# Bike_sharing_system_final_one_with_30_pi.net
KiCad netlist of a schematic drawn in EasyEDA
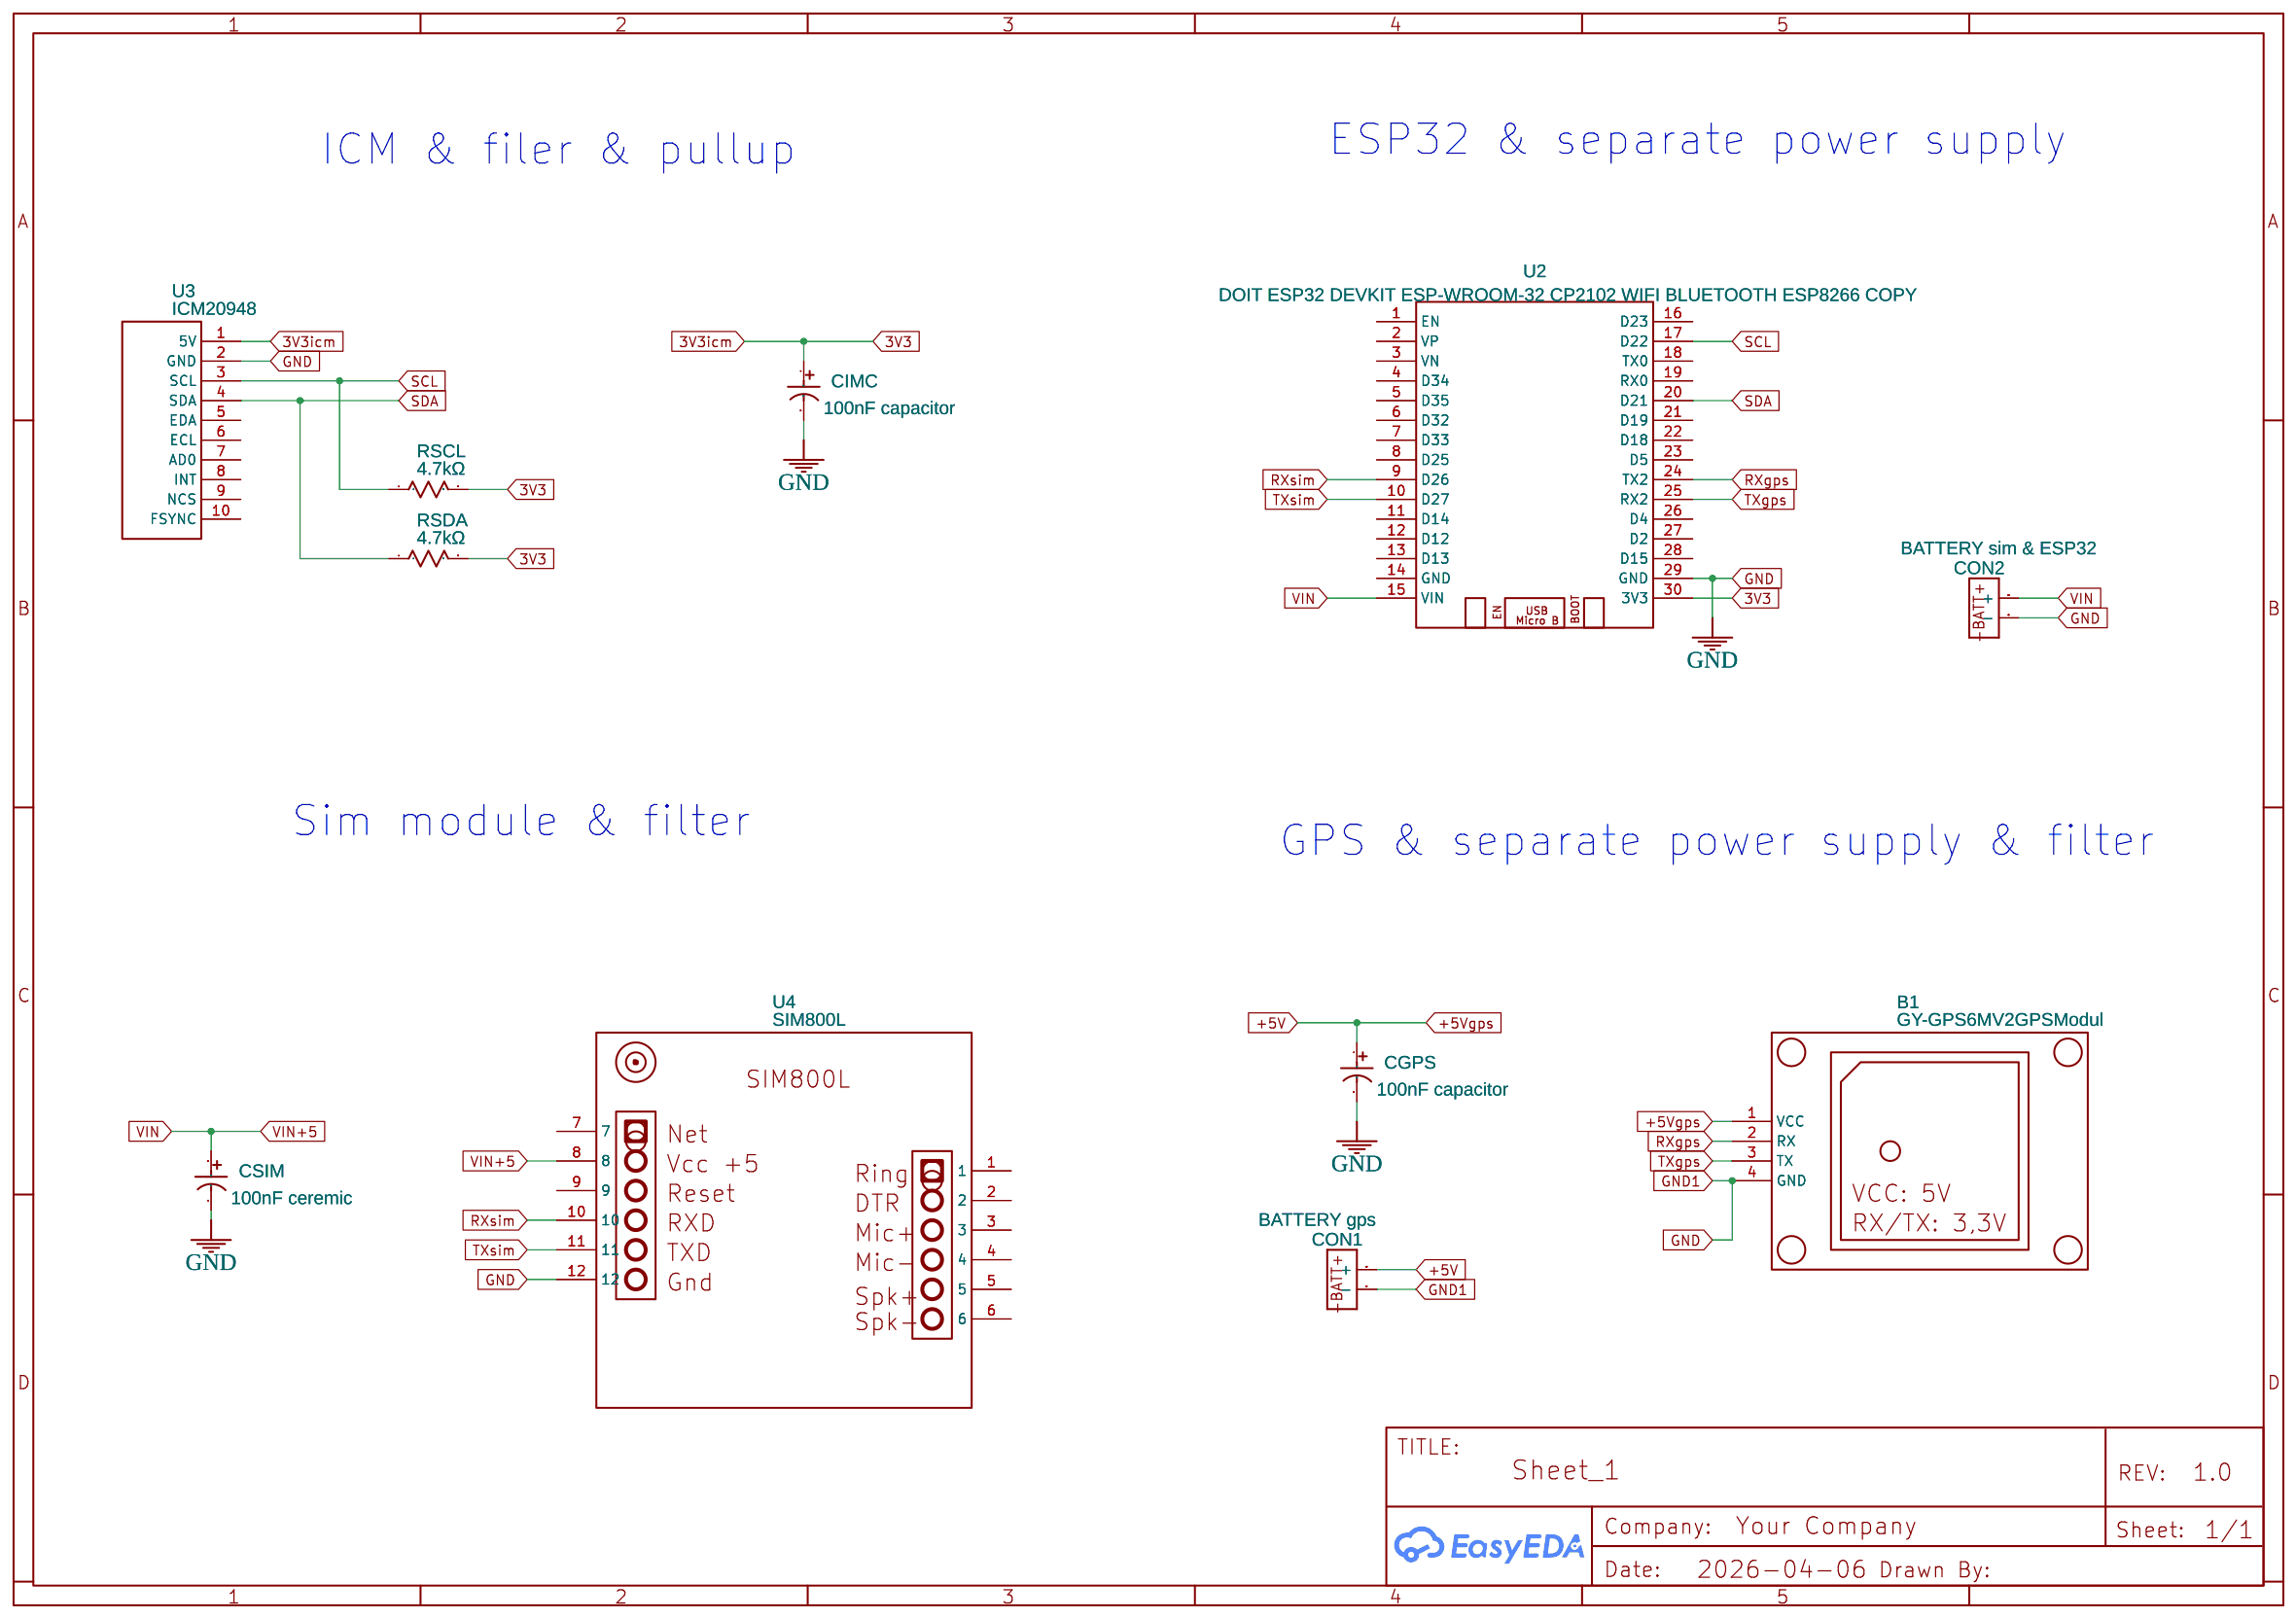
[diagram p0: schematic sheet]

(export (version "E")
  (design (tool "Eeschema 10.0.6"))
  (components
    (comp (ref "B1") (value "GY-GPS6MV2GPSModul") (libsource (lib "") (part "GY-GPS6MV2GPSModul")))
    (comp (ref "CGPS")
      (value "100nF capacitor")
      (fields
        (field (name "Manufacturer Part") "KM476M016D11RR0VH2FP0")
        (field (name "Manufacturer") "CX(承兴)")
      )
      (libsource (lib "") (part "CAPACITOR 680UF COPY"))
    )
    (comp (ref "CIMC")
      (value "100nF capacitor")
      (fields
        (field (name "Manufacturer Part") "KM476M016D11RR0VH2FP0")
        (field (name "Manufacturer") "CX(承兴)")
      )
      (libsource (lib "") (part "CAPACITOR 680UF COPY_2"))
    )
    (comp (ref "CON1") (value "BATTERY gps") (libsource (lib "") (part "2 PIN CON (BATTERY)")))
    (comp (ref "CON2") (value "BATTERY sim & ESP32") (libsource (lib "") (part "2 PIN CON (BATTERY)")))
    (comp (ref "CSIM")
      (value "100nF ceremic")
      (fields
        (field (name "Manufacturer Part") "KM476M016D11RR0VH2FP0")
        (field (name "Manufacturer") "CX(承兴)")
      )
      (libsource (lib "") (part "CAPACITOR 680UF COPY_1"))
    )
    (comp (ref "RSCL")
      (value "4.7kΩ")
      (fields (field (name "Manufacturer Part") "Resister"))
      (libsource (lib "") (part "RESISTER COPY_1"))
    )
    (comp (ref "RSDA")
      (value "4.7kΩ")
      (fields (field (name "Manufacturer Part") "Resister"))
      (libsource (lib "") (part "RESISTER COPY"))
    )
    (comp (ref "U2")
      (value "DOIT ESP32 DEVKIT ESP-WROOM-32 CP2102 WIFI BLUETOOTH ESP8266 COPY")
      (libsource (lib "") (part "DOIT ESP32 DEVKIT ESP-WROOM-32 CP2102 WIFI BLUETOOTH ESP8266 COPY"))
    )
    (comp (ref "U3") (value "ICM20948") (libsource (lib "") (part "ICM20948")))
    (comp (ref "U4") (value "SIM800L") (libsource (lib "") (part "SIM800L")))
  )
  (nets
    (net (code "1") (name "+5V") (class "Default")
      (node (ref "B1") (pin "1") (pinfunction "VCC_1") (pintype "unspecified"))
      (node (ref "CGPS") (pin "1") (pinfunction "1_1") (pintype "unspecified"))
      (node (ref "CON1") (pin "BAT+") (pinfunction "+_BAT+") (pintype "unspecified"))
    )
    (net (code "2") (name "3V3") (class "Default")
      (node (ref "CIMC") (pin "1") (pinfunction "1_1") (pintype "unspecified"))
      (node (ref "RSCL") (pin "2") (pinfunction "2_2") (pintype "unspecified"))
      (node (ref "RSDA") (pin "2") (pinfunction "2_2") (pintype "unspecified"))
      (node (ref "U2") (pin "30") (pinfunction "3V3_30") (pintype "bidirectional"))
      (node (ref "U3") (pin "1") (pinfunction "5V_1") (pintype "unspecified"))
    )
    (net (code "3") (name "GND") (class "Default")
      (node (ref "B1") (pin "4") (pinfunction "GND_4") (pintype "unspecified"))
      (node (ref "CGPS") (pin "2") (pinfunction "2_2") (pintype "unspecified"))
      (node (ref "CIMC") (pin "2") (pinfunction "2_2") (pintype "unspecified"))
      (node (ref "CON1") (pin "BAT-") (pinfunction "-_BAT-") (pintype "unspecified"))
      (node (ref "CON2") (pin "BAT-") (pinfunction "-_BAT-") (pintype "unspecified"))
      (node (ref "CSIM") (pin "2") (pinfunction "2_2") (pintype "unspecified"))
      (node (ref "U2") (pin "29") (pinfunction "GND_29") (pintype "bidirectional"))
      (node (ref "U3") (pin "2") (pinfunction "GND_2") (pintype "unspecified"))
      (node (ref "U4") (pin "12") (pinfunction "12_12") (pintype "unspecified"))
    )
    (net (code "4") (name "RXgps") (class "Default")
      (node (ref "B1") (pin "2") (pinfunction "RX_2") (pintype "unspecified"))
      (node (ref "U2") (pin "24") (pinfunction "TX2_24") (pintype "bidirectional"))
    )
    (net (code "5") (name "RXsim") (class "Default")
      (node (ref "U2") (pin "9") (pinfunction "D26_9") (pintype "bidirectional"))
      (node (ref "U4") (pin "10") (pinfunction "10_10") (pintype "unspecified"))
    )
    (net (code "6") (name "SCL") (class "Default")
      (node (ref "RSCL") (pin "1") (pinfunction "1_1") (pintype "unspecified"))
      (node (ref "U2") (pin "17") (pinfunction "D22_17") (pintype "bidirectional"))
      (node (ref "U3") (pin "3") (pinfunction "SCL_3") (pintype "unspecified"))
    )
    (net (code "7") (name "SDA") (class "Default")
      (node (ref "RSDA") (pin "1") (pinfunction "1_1") (pintype "unspecified"))
      (node (ref "U2") (pin "20") (pinfunction "D21_20") (pintype "bidirectional"))
      (node (ref "U3") (pin "4") (pinfunction "SDA_4") (pintype "unspecified"))
    )
    (net (code "8") (name "TXgps") (class "Default")
      (node (ref "B1") (pin "3") (pinfunction "TX_3") (pintype "unspecified"))
      (node (ref "U2") (pin "25") (pinfunction "RX2_25") (pintype "bidirectional"))
    )
    (net (code "9") (name "TXsim") (class "Default")
      (node (ref "U2") (pin "10") (pinfunction "D27_10") (pintype "bidirectional"))
      (node (ref "U4") (pin "11") (pinfunction "11_11") (pintype "unspecified"))
    )
    (net (code "10") (name "VIN") (class "Default")
      (node (ref "CON2") (pin "BAT+") (pinfunction "+_BAT+") (pintype "unspecified"))
      (node (ref "CSIM") (pin "1") (pinfunction "1_1") (pintype "unspecified"))
      (node (ref "U2") (pin "15") (pinfunction "VIN_15") (pintype "input"))
      (node (ref "U4") (pin "8") (pinfunction "8_8") (pintype "unspecified"))
    )
    (net (code "11") (name "unconnected-(U2-D2-Pad27)") (class "Default")
      (node (ref "U2") (pin "27") (pinfunction "D2_27") (pintype "bidirectional"))
    )
    (net (code "12") (name "unconnected-(U2-D4-Pad26)") (class "Default")
      (node (ref "U2") (pin "26") (pinfunction "D4_26") (pintype "bidirectional"))
    )
    (net (code "13") (name "unconnected-(U2-D5-Pad23)") (class "Default")
      (node (ref "U2") (pin "23") (pinfunction "D5_23") (pintype "bidirectional"))
    )
    (net (code "14") (name "unconnected-(U2-D12-Pad12)") (class "Default")
      (node (ref "U2") (pin "12") (pinfunction "D12_12") (pintype "bidirectional"))
    )
    (net (code "15") (name "unconnected-(U2-D13-Pad13)") (class "Default")
      (node (ref "U2") (pin "13") (pinfunction "D13_13") (pintype "bidirectional"))
    )
    (net (code "16") (name "unconnected-(U2-D14-Pad11)") (class "Default")
      (node (ref "U2") (pin "11") (pinfunction "D14_11") (pintype "bidirectional"))
    )
    (net (code "17") (name "unconnected-(U2-D15-Pad28)") (class "Default")
      (node (ref "U2") (pin "28") (pinfunction "D15_28") (pintype "bidirectional"))
    )
    (net (code "18") (name "unconnected-(U2-D18-Pad22)") (class "Default")
      (node (ref "U2") (pin "22") (pinfunction "D18_22") (pintype "bidirectional"))
    )
    (net (code "19") (name "unconnected-(U2-D19-Pad21)") (class "Default")
      (node (ref "U2") (pin "21") (pinfunction "D19_21") (pintype "bidirectional"))
    )
    (net (code "20") (name "unconnected-(U2-D23-Pad16)") (class "Default")
      (node (ref "U2") (pin "16") (pinfunction "D23_16") (pintype "bidirectional"))
    )
    (net (code "21") (name "unconnected-(U2-D25-Pad8)") (class "Default")
      (node (ref "U2") (pin "8") (pinfunction "D25_8") (pintype "bidirectional"))
    )
    (net (code "22") (name "unconnected-(U2-D32-Pad6)") (class "Default")
      (node (ref "U2") (pin "6") (pinfunction "D32_6") (pintype "bidirectional"))
    )
    (net (code "23") (name "unconnected-(U2-D33-Pad7)") (class "Default")
      (node (ref "U2") (pin "7") (pinfunction "D33_7") (pintype "bidirectional"))
    )
    (net (code "24") (name "unconnected-(U2-D34-Pad4)") (class "Default")
      (node (ref "U2") (pin "4") (pinfunction "D34_4") (pintype "input"))
    )
    (net (code "25") (name "unconnected-(U2-D35-Pad5)") (class "Default")
      (node (ref "U2") (pin "5") (pinfunction "D35_5") (pintype "input"))
    )
    (net (code "26") (name "unconnected-(U2-EN-Pad1)") (class "Default")
      (node (ref "U2") (pin "1") (pinfunction "EN_1") (pintype "bidirectional"))
    )
    (net (code "27") (name "unconnected-(U2-GND-Pad14)") (class "Default")
      (node (ref "U2") (pin "14") (pinfunction "GND_14") (pintype "bidirectional"))
    )
    (net (code "28") (name "unconnected-(U2-RX0-Pad19)") (class "Default")
      (node (ref "U2") (pin "19") (pinfunction "RX0_19") (pintype "bidirectional"))
    )
    (net (code "29") (name "unconnected-(U2-TX0-Pad18)") (class "Default")
      (node (ref "U2") (pin "18") (pinfunction "TX0_18") (pintype "bidirectional"))
    )
    (net (code "30") (name "unconnected-(U2-VN-Pad3)") (class "Default")
      (node (ref "U2") (pin "3") (pinfunction "VN_3") (pintype "input"))
    )
    (net (code "31") (name "unconnected-(U2-VP-Pad2)") (class "Default")
      (node (ref "U2") (pin "2") (pinfunction "VP_2") (pintype "input"))
    )
    (net (code "32") (name "unconnected-(U3-AD0-Pad7)") (class "Default")
      (node (ref "U3") (pin "7") (pinfunction "AD0_7") (pintype "unspecified"))
    )
    (net (code "33") (name "unconnected-(U3-ECL-Pad6)") (class "Default")
      (node (ref "U3") (pin "6") (pinfunction "ECL_6") (pintype "unspecified"))
    )
    (net (code "34") (name "unconnected-(U3-EDA-Pad5)") (class "Default")
      (node (ref "U3") (pin "5") (pinfunction "EDA_5") (pintype "unspecified"))
    )
    (net (code "35") (name "unconnected-(U3-FSYNC-Pad10)") (class "Default")
      (node (ref "U3") (pin "10") (pinfunction "FSYNC_10") (pintype "unspecified"))
    )
    (net (code "36") (name "unconnected-(U3-INT-Pad8)") (class "Default")
      (node (ref "U3") (pin "8") (pinfunction "INT_8") (pintype "unspecified"))
    )
    (net (code "37") (name "unconnected-(U3-NCS-Pad9)") (class "Default")
      (node (ref "U3") (pin "9") (pinfunction "NCS_9") (pintype "unspecified"))
    )
    (net (code "38") (name "unconnected-(U4-Pad1)") (class "Default")
      (node (ref "U4") (pin "1") (pinfunction "1_1") (pintype "unspecified"))
    )
    (net (code "39") (name "unconnected-(U4-Pad2)") (class "Default")
      (node (ref "U4") (pin "2") (pinfunction "2_2") (pintype "unspecified"))
    )
    (net (code "40") (name "unconnected-(U4-Pad3)") (class "Default")
      (node (ref "U4") (pin "3") (pinfunction "3_3") (pintype "unspecified"))
    )
    (net (code "41") (name "unconnected-(U4-Pad4)") (class "Default")
      (node (ref "U4") (pin "4") (pinfunction "4_4") (pintype "unspecified"))
    )
    (net (code "42") (name "unconnected-(U4-Pad5)") (class "Default")
      (node (ref "U4") (pin "5") (pinfunction "5_5") (pintype "unspecified"))
    )
    (net (code "43") (name "unconnected-(U4-Pad6)") (class "Default")
      (node (ref "U4") (pin "6") (pinfunction "6_6") (pintype "unspecified"))
    )
    (net (code "44") (name "unconnected-(U4-Pad7)") (class "Default")
      (node (ref "U4") (pin "7") (pinfunction "7_7") (pintype "unspecified"))
    )
    (net (code "45") (name "unconnected-(U4-Pad9)") (class "Default")
      (node (ref "U4") (pin "9") (pinfunction "9_9") (pintype "unspecified"))
    )
  )
)
